# Singularitron_Laser_Module.net
KiCad netlist of a schematic drawn in EAGLE
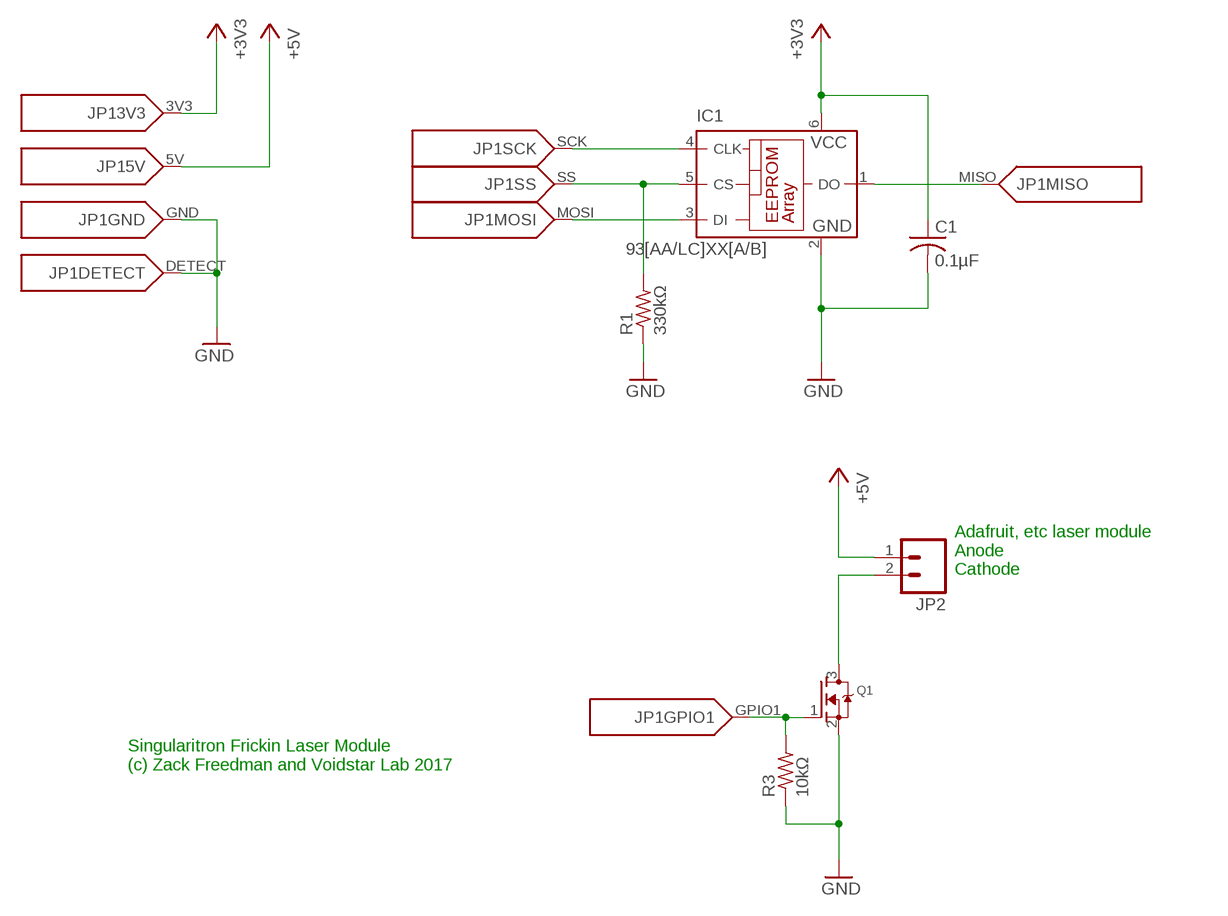
[diagram p0: schematic, sheet 1]

(export (version "E")
  (design (tool "Eeschema 10.0.6"))
  (components
    (comp (ref "C1")
      (value "0.1µF")
      (footprint "eagle-import:C0603")
      (libsource (lib "eagle-import") (part "C-USC0603"))
    )
    (comp (ref "IC1")
      (value "93[AA/LC]XX[A/B]")
      (footprint "eagle-import:SOT23-6")
      (fields (field (name "MPN") "93AA76AT-I/OT"))
      (libsource (lib "eagle-import") (part "9376?AAA"))
    )
    (comp (ref "JP1")
      (value "SINGULARITRON_CART_BASE")
      (footprint "eagle-import:SINGULARITRON_CART_BASE")
      (libsource (lib "eagle-import") (part "SINGULARITRON_CART_BASE"))
    )
    (comp (ref "JP2")
      (value "M02PTH")
      (footprint "eagle-import:1X02")
      (libsource (lib "eagle-import") (part "M02PTH"))
    )
    (comp (ref "Q1")
      (value "MOSFET-NREFLOW")
      (footprint "eagle-import:SOT23")
      (libsource (lib "eagle-import") (part "MOSFET-NREFLOW"))
    )
    (comp (ref "R1")
      (value "330kΩ")
      (footprint "eagle-import:R0603")
      (libsource (lib "eagle-import") (part "R-US_R0603"))
    )
    (comp (ref "R3")
      (value "10kΩ")
      (footprint "eagle-import:R0603")
      (libsource (lib "eagle-import") (part "R-US_R0603"))
    )
  )
  (nets
    (net (code "1") (name "+3V3") (class "Default")
      (node (ref "C1") (pin "1") (pinfunction "1_1") (pintype "passive"))
      (node (ref "IC1") (pin "6") (pinfunction "VCC_6") (pintype "power_in"))
      (node (ref "JP1") (pin "3V3") (pinfunction "P$1_3V3") (pintype "bidirectional"))
    )
    (net (code "2") (name "+5V") (class "Default")
      (node (ref "JP1") (pin "5V") (pinfunction "P$1_5V") (pintype "bidirectional"))
      (node (ref "JP2") (pin "1") (pinfunction "1_1") (pintype "passive"))
    )
    (net (code "3") (name "GND") (class "Default")
      (node (ref "C1") (pin "2") (pinfunction "2_2") (pintype "passive"))
      (node (ref "IC1") (pin "2") (pinfunction "GND_2") (pintype "power_in"))
      (node (ref "JP1") (pin "DETECT") (pinfunction "P$1_DETECT") (pintype "bidirectional"))
      (node (ref "JP1") (pin "GND") (pinfunction "P$1_GND") (pintype "bidirectional"))
      (node (ref "Q1") (pin "2") (pinfunction "S_2") (pintype "bidirectional"))
      (node (ref "R1") (pin "1") (pinfunction "1_1") (pintype "passive"))
      (node (ref "R3") (pin "1") (pinfunction "1_1") (pintype "passive"))
    )
    (net (code "4") (name "Net-(IC1-CLK)") (class "Default")
      (node (ref "IC1") (pin "4") (pinfunction "CLK_4") (pintype "input"))
      (node (ref "JP1") (pin "SCK") (pinfunction "P$1_SCK") (pintype "bidirectional"))
    )
    (net (code "5") (name "Net-(IC1-CS)") (class "Default")
      (node (ref "IC1") (pin "5") (pinfunction "CS_5") (pintype "input"))
      (node (ref "JP1") (pin "SS") (pinfunction "P$1_SS") (pintype "bidirectional"))
      (node (ref "R1") (pin "2") (pinfunction "2_2") (pintype "passive"))
    )
    (net (code "6") (name "Net-(IC1-DI)") (class "Default")
      (node (ref "IC1") (pin "3") (pinfunction "DI_3") (pintype "input"))
      (node (ref "JP1") (pin "MOSI") (pinfunction "P$1_MOSI") (pintype "bidirectional"))
    )
    (net (code "7") (name "Net-(IC1-DO)") (class "Default")
      (node (ref "IC1") (pin "1") (pinfunction "DO_1") (pintype "tri_state"))
      (node (ref "JP1") (pin "MISO") (pinfunction "P$1_MISO") (pintype "bidirectional"))
    )
    (net (code "8") (name "Net-(JP1E-P$1)") (class "Default")
      (node (ref "JP1") (pin "GPIO1") (pinfunction "P$1_GPIO1") (pintype "bidirectional"))
      (node (ref "Q1") (pin "1") (pinfunction "G_1") (pintype "bidirectional"))
      (node (ref "R3") (pin "2") (pinfunction "2_2") (pintype "passive"))
    )
    (net (code "9") (name "Net-(Q1-D)") (class "Default")
      (node (ref "JP2") (pin "2") (pinfunction "2_2") (pintype "passive"))
      (node (ref "Q1") (pin "3") (pinfunction "D_3") (pintype "bidirectional"))
    )
  )
)
